# pt100.net
KiCad netlist of a schematic drawn in Altium Designer
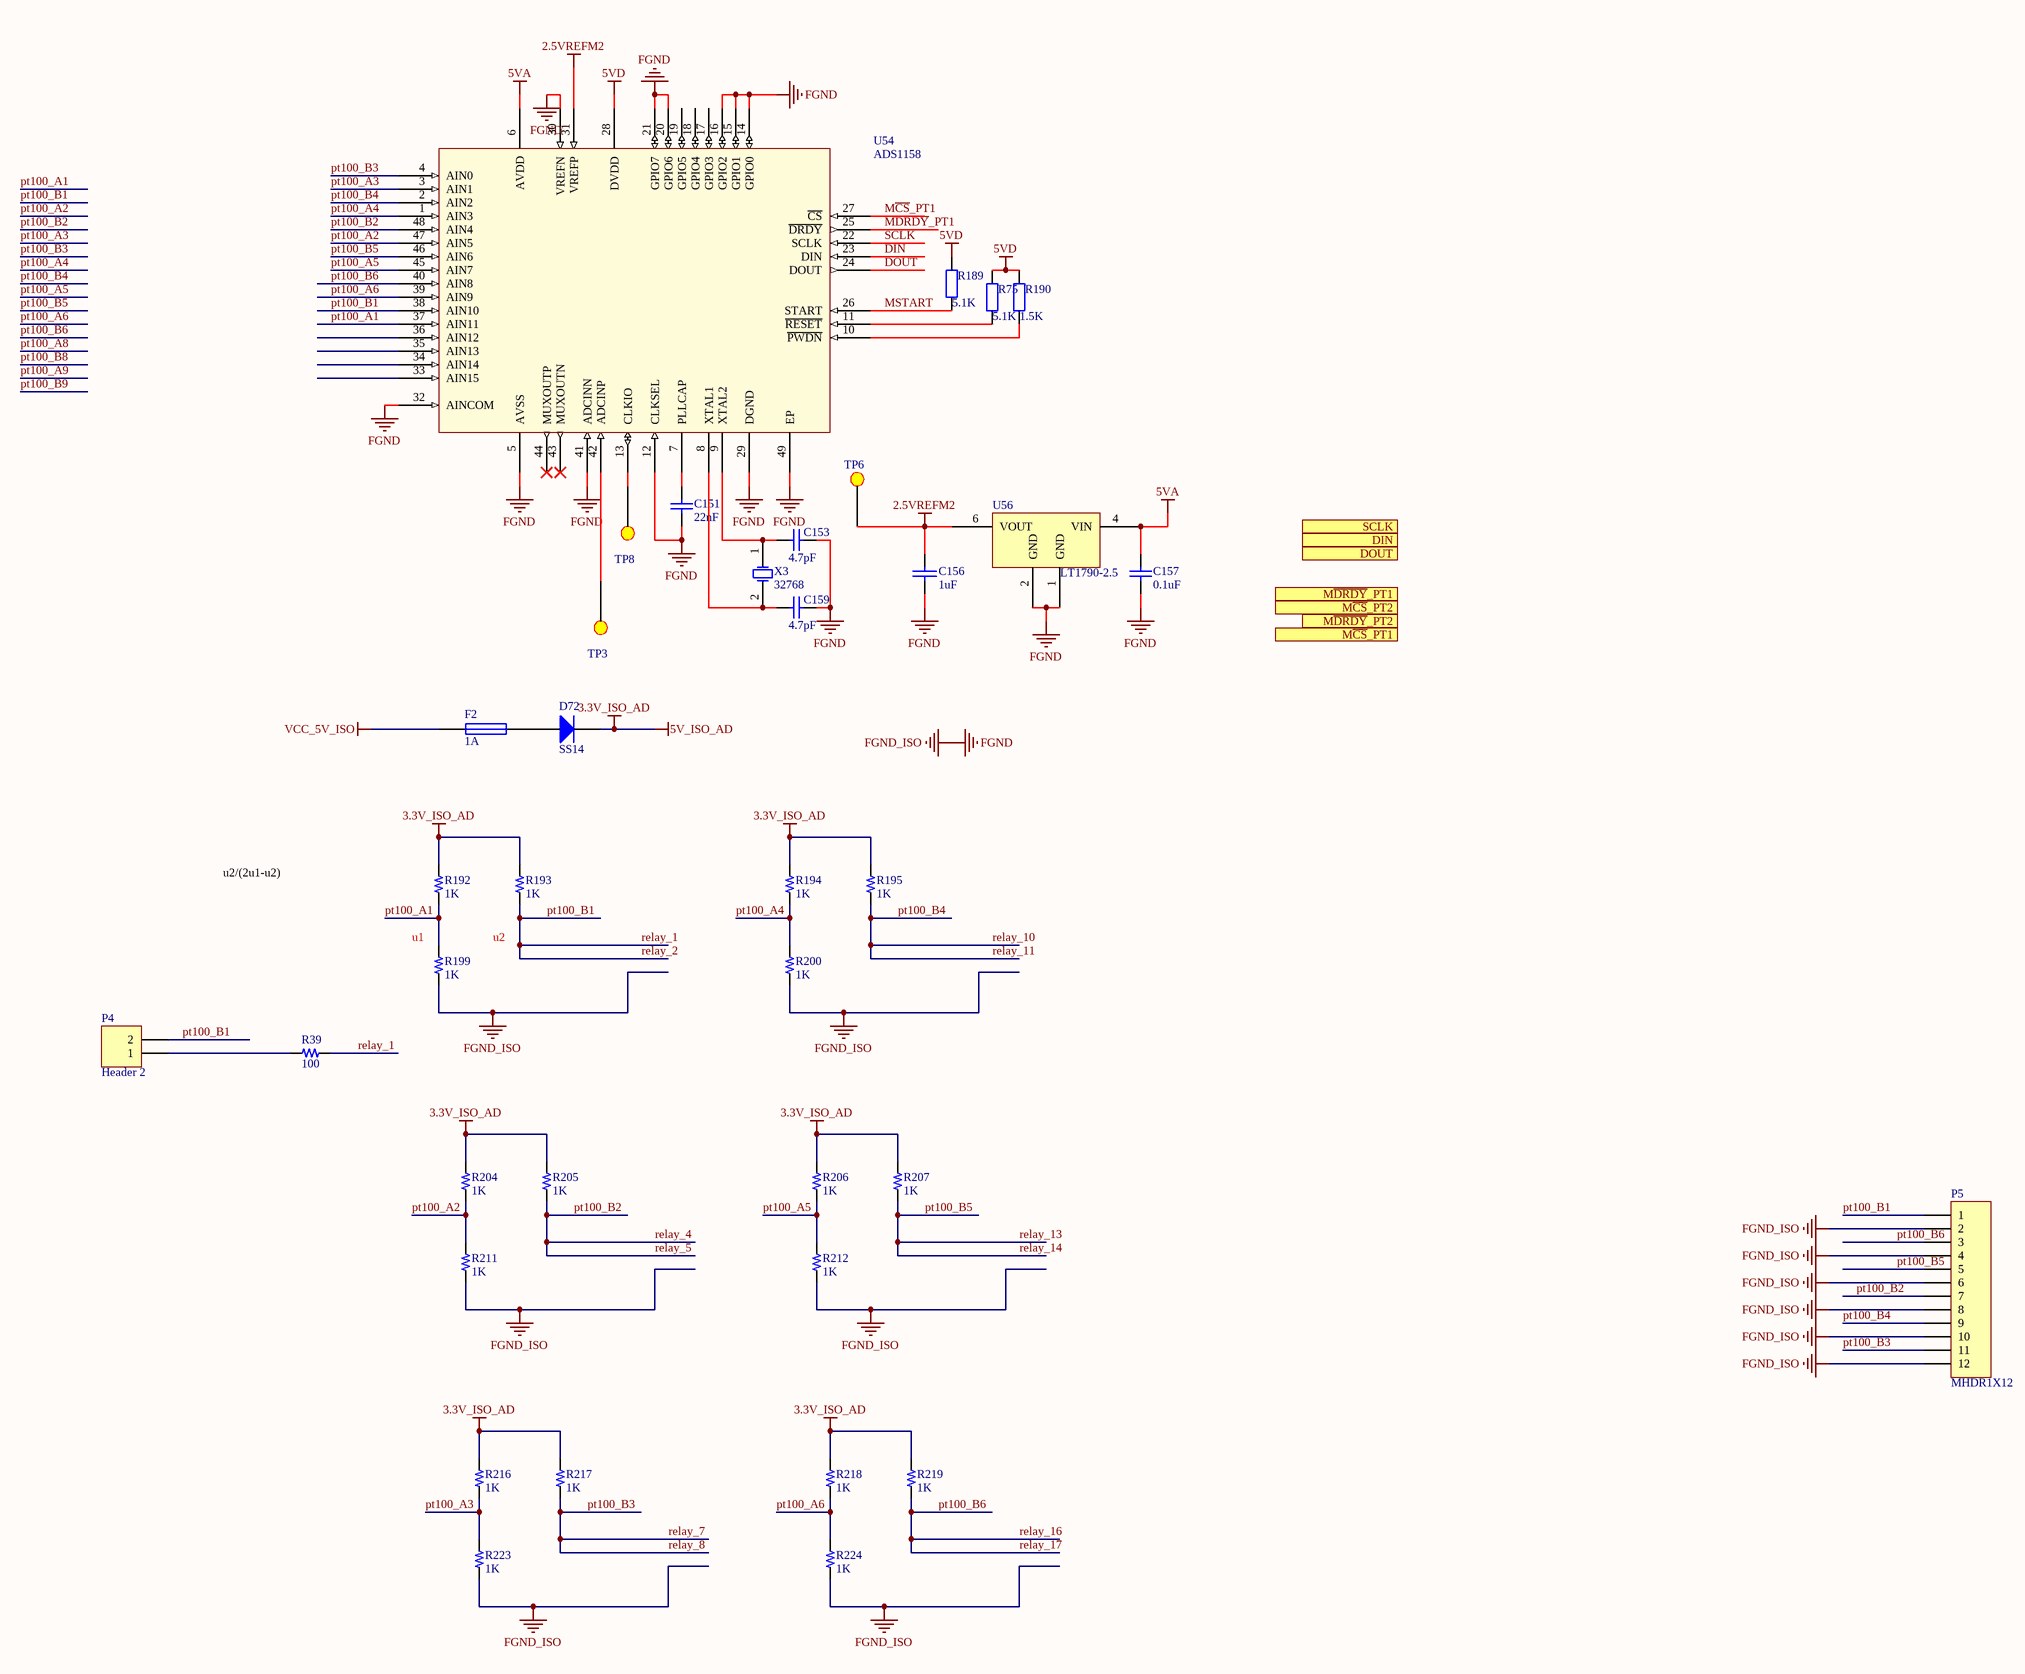
[diagram p0: pt100.SchDoc]

(export (version "E")
  (design (tool "Eeschema 10.0.6"))
  (components
    (comp (ref "C151")
      (value "22nF")
      (footprint "0805C")
      (description "Capacitor")
      (fields (field (name "PUBLISHER") "Altium Limited"))
      (libsource (lib "Miscellaneous Devices") (part "Cap"))
    )
    (comp (ref "C153")
      (value "4.7pF")
      (footprint "0603C")
      (description "Capacitor")
      (fields (field (name "PUBLISHER") "Altium Limited"))
      (libsource (lib "Miscellaneous Devices") (part "Cap"))
    )
    (comp (ref "C156")
      (value "1uF")
      (footprint "0603C")
      (description "Capacitor")
      (libsource (lib "*") (part "CAP"))
    )
    (comp (ref "C157")
      (value "0.1uF")
      (footprint "0603C")
      (description "Capacitor")
      (fields (field (name "PUBLISHER") "Altium Limited"))
      (libsource (lib "Miscellaneous Devices") (part "Cap"))
    )
    (comp (ref "C159")
      (value "4.7pF")
      (footprint "0603C")
      (description "Capacitor")
      (fields (field (name "PUBLISHER") "Altium Limited"))
      (libsource (lib "Miscellaneous Devices") (part "Cap"))
    )
    (comp (ref "D72")
      (value "SS14")
      (footprint "DO-214AC")
      (description "Default Diode")
      (fields (field (name "PUBLISHER") "Altium Limited"))
      (libsource (lib "Miscellaneous Devices") (part "Diode"))
    )
    (comp (ref "F2")
      (value "1A")
      (footprint "0805r")
      (description "Fuse")
      (fields (field (name "PUBLISHER") "Altium Limited"))
      (libsource (lib "Miscellaneous Devices") (part "Fuse 1"))
    )
    (comp (ref "P4")
      (value "Header 2")
      (footprint "HDR1X2")
      (description "Header, 2-Pin")
      (fields (field (name "PUBLISHER") "Altium Limited"))
      (libsource (lib "Miscellaneous Connectors") (part "Header 2"))
    )
    (comp (ref "P5")
      (value "MHDR1X12")
      (footprint "2ETYR-5.08-12P-14-100")
      (description "Header, 12-Pin")
      (fields (field (name "PUBLISHER") "Altium Limited"))
      (libsource (lib "Miscellaneous Connectors") (part "MHDR1X12"))
    )
    (comp (ref "R39")
      (value "100")
      (footprint "0603R")
      (description "R")
      (libsource (lib "JRJ_1") (part "R"))
    )
    (comp (ref "R75") (value "5.1K") (footprint "0603R") (libsource (lib "MQlibrary") (part "Res0805M")))
    (comp (ref "R189") (value "5.1K") (footprint "0603R") (libsource (lib "MQlibrary") (part "Res0805M")))
    (comp (ref "R190") (value "1.5K") (footprint "0603R") (libsource (lib "MQlibrary") (part "Res0805M")))
    (comp (ref "R192")
      (value "1K")
      (footprint "0603R")
      (description "R")
      (libsource (lib "JRJ_1") (part "R"))
    )
    (comp (ref "R193")
      (value "1K")
      (footprint "0603R")
      (description "R")
      (libsource (lib "JRJ_1") (part "R"))
    )
    (comp (ref "R194")
      (value "1K")
      (footprint "0603R")
      (description "R")
      (libsource (lib "JRJ_1") (part "R"))
    )
    (comp (ref "R195")
      (value "1K")
      (footprint "0603R")
      (description "R")
      (libsource (lib "JRJ_1") (part "R"))
    )
    (comp (ref "R199")
      (value "1K")
      (footprint "0603R")
      (description "R")
      (libsource (lib "JRJ_1") (part "R"))
    )
    (comp (ref "R200")
      (value "1K")
      (footprint "0603R")
      (description "R")
      (libsource (lib "JRJ_1") (part "R"))
    )
    (comp (ref "R204")
      (value "1K")
      (footprint "0603R")
      (description "R")
      (libsource (lib "JRJ_1") (part "R"))
    )
    (comp (ref "R205")
      (value "1K")
      (footprint "0603R")
      (description "R")
      (libsource (lib "JRJ_1") (part "R"))
    )
    (comp (ref "R206")
      (value "1K")
      (footprint "0603R")
      (description "R")
      (libsource (lib "JRJ_1") (part "R"))
    )
    (comp (ref "R207")
      (value "1K")
      (footprint "0603R")
      (description "R")
      (libsource (lib "JRJ_1") (part "R"))
    )
    (comp (ref "R211")
      (value "1K")
      (footprint "0603R")
      (description "R")
      (libsource (lib "JRJ_1") (part "R"))
    )
    (comp (ref "R212")
      (value "1K")
      (footprint "0603R")
      (description "R")
      (libsource (lib "JRJ_1") (part "R"))
    )
    (comp (ref "R216")
      (value "1K")
      (footprint "0603R")
      (description "R")
      (libsource (lib "JRJ_1") (part "R"))
    )
    (comp (ref "R217")
      (value "1K")
      (footprint "0603R")
      (description "R")
      (libsource (lib "JRJ_1") (part "R"))
    )
    (comp (ref "R218")
      (value "1K")
      (footprint "0603R")
      (description "R")
      (libsource (lib "JRJ_1") (part "R"))
    )
    (comp (ref "R219")
      (value "1K")
      (footprint "0603R")
      (description "R")
      (libsource (lib "JRJ_1") (part "R"))
    )
    (comp (ref "R223")
      (value "1K")
      (footprint "0603R")
      (description "R")
      (libsource (lib "JRJ_1") (part "R"))
    )
    (comp (ref "R224")
      (value "1K")
      (footprint "0603R")
      (description "R")
      (libsource (lib "JRJ_1") (part "R"))
    )
    (comp (ref "TP3")
      (value "TEST_POINT")
      (footprint "TPD")
      (libsource (lib "基带芯片OEM板_V1P0_张猛_20120921") (part "TEST_POINT"))
    )
    (comp (ref "TP6")
      (value "TEST_POINT")
      (footprint "TPD")
      (libsource (lib "基带芯片OEM板_V1P0_张猛_20120921") (part "TEST_POINT"))
    )
    (comp (ref "TP8")
      (value "TEST_POINT")
      (footprint "TPD")
      (libsource (lib "基带芯片OEM板_V1P0_张猛_20120921") (part "TEST_POINT"))
    )
    (comp (ref "U54")
      (value "ADS1158")
      (footprint "S-PVFQN-N48")
      (description "16-Channel, 16-Bit Analog-to-Digital Converter")
      (libsource (lib "Schlib") (part "ADS1158"))
    )
    (comp (ref "U56")
      (value "LT1790-2.5")
      (footprint "SOT23-6")
      (description "2.5V Micropower SOT-23  Low Dropout Reference")
      (libsource (lib "Schlib") (part "LT1790-2.5"))
    )
    (comp (ref "X3")
      (value "32768")
      (footprint "A")
      (description "Crystal Oscillator")
      (fields (field (name "PUBLISHER") "Altium Limited"))
      (libsource (lib "Miscellaneous Devices") (part "XTAL"))
    )
  )
  (nets
    (net (code "1") (name "/DIN") (class "Default")
      (node (ref "U54") (pin "23") (pinfunction "DIN_23") (pintype "input"))
    )
    (net (code "2") (name "/DOUT") (class "Default")
      (node (ref "U54") (pin "24") (pinfunction "DOUT_24") (pintype "output"))
    )
    (net (code "3") (name "/MSTART") (class "Default")
      (node (ref "R189") (pin "2") (pinfunction "2_2") (pintype "passive"))
      (node (ref "U54") (pin "26") (pinfunction "START_26") (pintype "input"))
    )
    (net (code "4") (name "/M~{CS}_PT1") (class "Default")
      (node (ref "U54") (pin "27") (pinfunction "~{CS}_27") (pintype "input"))
    )
    (net (code "6") (name "/M~{DRDY}_PT1") (class "Default")
      (node (ref "U54") (pin "25") (pinfunction "~{DRDY}_25") (pintype "output"))
    )
    (net (code "8") (name "/SCLK") (class "Default")
      (node (ref "U54") (pin "22") (pinfunction "SCLK_22") (pintype "input"))
    )
    (net (code "9") (name "/pt100_A1") (class "Default")
      (node (ref "R192") (pin "1") (pintype "passive"))
      (node (ref "R199") (pin "2") (pintype "passive"))
      (node (ref "U54") (pin "37") (pinfunction "AIN11_37") (pintype "input"))
    )
    (net (code "10") (name "/pt100_A2") (class "Default")
      (node (ref "R204") (pin "1") (pintype "passive"))
      (node (ref "R211") (pin "2") (pintype "passive"))
      (node (ref "U54") (pin "47") (pinfunction "AIN5_47") (pintype "input"))
    )
    (net (code "11") (name "/pt100_A3") (class "Default")
      (node (ref "R216") (pin "1") (pintype "passive"))
      (node (ref "R223") (pin "2") (pintype "passive"))
      (node (ref "U54") (pin "3") (pinfunction "AIN1_3") (pintype "input"))
    )
    (net (code "12") (name "/pt100_A4") (class "Default")
      (node (ref "R194") (pin "1") (pintype "passive"))
      (node (ref "R200") (pin "2") (pintype "passive"))
      (node (ref "U54") (pin "1") (pinfunction "AIN3_1") (pintype "input"))
    )
    (net (code "13") (name "/pt100_A5") (class "Default")
      (node (ref "R206") (pin "1") (pintype "passive"))
      (node (ref "R212") (pin "2") (pintype "passive"))
      (node (ref "U54") (pin "45") (pinfunction "AIN7_45") (pintype "input"))
    )
    (net (code "14") (name "/pt100_A6") (class "Default")
      (node (ref "R218") (pin "1") (pintype "passive"))
      (node (ref "R224") (pin "2") (pintype "passive"))
      (node (ref "U54") (pin "39") (pinfunction "AIN9_39") (pintype "input"))
    )
    (net (code "17") (name "/pt100_B1") (class "Default")
      (node (ref "P4") (pin "2") (pinfunction "2_2") (pintype "passive"))
      (node (ref "P5") (pin "1") (pinfunction "1_1") (pintype "passive"))
      (node (ref "R193") (pin "1") (pintype "passive"))
      (node (ref "R39") (pin "1") (pintype "passive"))
      (node (ref "U54") (pin "38") (pinfunction "AIN10_38") (pintype "input"))
    )
    (net (code "18") (name "/pt100_B2") (class "Default")
      (node (ref "P5") (pin "7") (pinfunction "7_7") (pintype "passive"))
      (node (ref "R205") (pin "1") (pintype "passive"))
      (node (ref "U54") (pin "48") (pinfunction "AIN4_48") (pintype "input"))
    )
    (net (code "19") (name "/pt100_B3") (class "Default")
      (node (ref "P5") (pin "11") (pinfunction "11_11") (pintype "passive"))
      (node (ref "R217") (pin "1") (pintype "passive"))
      (node (ref "U54") (pin "4") (pinfunction "AIN0_4") (pintype "input"))
    )
    (net (code "20") (name "/pt100_B4") (class "Default")
      (node (ref "P5") (pin "9") (pinfunction "9_9") (pintype "passive"))
      (node (ref "R195") (pin "1") (pintype "passive"))
      (node (ref "U54") (pin "2") (pinfunction "AIN2_2") (pintype "input"))
    )
    (net (code "21") (name "/pt100_B5") (class "Default")
      (node (ref "P5") (pin "5") (pinfunction "5_5") (pintype "passive"))
      (node (ref "R207") (pin "1") (pintype "passive"))
      (node (ref "U54") (pin "46") (pinfunction "AIN6_46") (pintype "input"))
    )
    (net (code "22") (name "/pt100_B6") (class "Default")
      (node (ref "P5") (pin "3") (pinfunction "3_3") (pintype "passive"))
      (node (ref "R219") (pin "1") (pintype "passive"))
      (node (ref "U54") (pin "40") (pinfunction "AIN8_40") (pintype "input"))
    )
    (net (code "25") (name "2.5VREFM2") (class "Default")
      (node (ref "C156") (pin "1") (pinfunction "1_1") (pintype "passive"))
      (node (ref "TP6") (pin "1") (pinfunction "1_1") (pintype "passive"))
      (node (ref "U54") (pin "31") (pinfunction "VREFP_31") (pintype "input"))
      (node (ref "U56") (pin "6") (pinfunction "VOUT_6") (pintype "power_in"))
    )
    (net (code "26") (name "3.3V_ISO_AD") (class "Default")
      (node (ref "D72") (pin "2") (pinfunction "K_2") (pintype "passive"))
      (node (ref "R192") (pin "2") (pintype "passive"))
      (node (ref "R193") (pin "2") (pintype "passive"))
      (node (ref "R194") (pin "2") (pintype "passive"))
      (node (ref "R195") (pin "2") (pintype "passive"))
      (node (ref "R204") (pin "2") (pintype "passive"))
      (node (ref "R205") (pin "2") (pintype "passive"))
      (node (ref "R206") (pin "2") (pintype "passive"))
      (node (ref "R207") (pin "2") (pintype "passive"))
      (node (ref "R216") (pin "2") (pintype "passive"))
      (node (ref "R217") (pin "2") (pintype "passive"))
      (node (ref "R218") (pin "2") (pintype "passive"))
      (node (ref "R219") (pin "2") (pintype "passive"))
    )
    (net (code "27") (name "5VA") (class "Default")
      (node (ref "C157") (pin "2") (pinfunction "2_2") (pintype "passive"))
      (node (ref "U54") (pin "6") (pinfunction "AVDD_6") (pintype "passive"))
      (node (ref "U56") (pin "4") (pinfunction "VIN_4") (pintype "power_in"))
    )
    (net (code "28") (name "5VD") (class "Default")
      (node (ref "R189") (pin "1") (pinfunction "1_1") (pintype "passive"))
      (node (ref "R190") (pin "1") (pinfunction "1_1") (pintype "passive"))
      (node (ref "R75") (pin "1") (pinfunction "1_1") (pintype "passive"))
      (node (ref "U54") (pin "28") (pinfunction "DVDD_28") (pintype "power_in"))
    )
    (net (code "29") (name "FGND") (class "Default")
      (node (ref "C151") (pin "2") (pinfunction "2_2") (pintype "passive"))
      (node (ref "C153") (pin "2") (pinfunction "2_2") (pintype "passive"))
      (node (ref "C156") (pin "2") (pinfunction "2_2") (pintype "passive"))
      (node (ref "C157") (pin "1") (pinfunction "1_1") (pintype "passive"))
      (node (ref "C159") (pin "2") (pinfunction "2_2") (pintype "passive"))
      (node (ref "P5") (pin "10") (pinfunction "10_10") (pintype "passive"))
      (node (ref "P5") (pin "12") (pinfunction "12_12") (pintype "passive"))
      (node (ref "P5") (pin "2") (pinfunction "2_2") (pintype "passive"))
      (node (ref "P5") (pin "4") (pinfunction "4_4") (pintype "passive"))
      (node (ref "P5") (pin "6") (pinfunction "6_6") (pintype "passive"))
      (node (ref "P5") (pin "8") (pinfunction "8_8") (pintype "passive"))
      (node (ref "R199") (pin "1") (pintype "passive"))
      (node (ref "R200") (pin "1") (pintype "passive"))
      (node (ref "R211") (pin "1") (pintype "passive"))
      (node (ref "R212") (pin "1") (pintype "passive"))
      (node (ref "R223") (pin "1") (pintype "passive"))
      (node (ref "R224") (pin "1") (pintype "passive"))
      (node (ref "U54") (pin "12") (pinfunction "CLKSEL_12") (pintype "input"))
      (node (ref "U54") (pin "14") (pinfunction "GPIO0_14") (pintype "bidirectional"))
      (node (ref "U54") (pin "15") (pinfunction "GPIO1_15") (pintype "bidirectional"))
      (node (ref "U54") (pin "16") (pinfunction "GPIO2_16") (pintype "bidirectional"))
      (node (ref "U54") (pin "20") (pinfunction "GPIO6_20") (pintype "bidirectional"))
      (node (ref "U54") (pin "21") (pinfunction "GPIO7_21") (pintype "bidirectional"))
      (node (ref "U54") (pin "29") (pinfunction "DGND_29") (pintype "power_in"))
      (node (ref "U54") (pin "30") (pinfunction "VREFN_30") (pintype "input"))
      (node (ref "U54") (pin "32") (pinfunction "AINCOM_32") (pintype "input"))
      (node (ref "U54") (pin "41") (pinfunction "ADCINN_41") (pintype "input"))
      (node (ref "U54") (pin "49") (pinfunction "EP_49") (pintype "passive"))
      (node (ref "U54") (pin "5") (pinfunction "AVSS_5") (pintype "power_in"))
      (node (ref "U56") (pin "1") (pinfunction "GND_1") (pintype "power_in"))
      (node (ref "U56") (pin "2") (pinfunction "GND_2") (pintype "power_in"))
    )
    (net (code "30") (name "Net-(D72-A)") (class "Default")
      (node (ref "D72") (pin "1") (pinfunction "A_1") (pintype "passive"))
      (node (ref "F2") (pin "2") (pinfunction "2_2") (pintype "passive"))
    )
    (net (code "31") (name "Net-(P4-Pad1)") (class "Default")
      (node (ref "P4") (pin "1") (pinfunction "1_1") (pintype "passive"))
      (node (ref "R39") (pin "2") (pintype "passive"))
    )
    (net (code "32") (name "Net-(U54-ADCINP)") (class "Default")
      (node (ref "TP3") (pin "1") (pinfunction "1_1") (pintype "passive"))
      (node (ref "U54") (pin "42") (pinfunction "ADCINP_42") (pintype "input"))
    )
    (net (code "33") (name "Net-(U54-CLKIO)") (class "Default")
      (node (ref "TP8") (pin "1") (pinfunction "1_1") (pintype "passive"))
      (node (ref "U54") (pin "13") (pinfunction "CLKIO_13") (pintype "bidirectional"))
    )
    (net (code "34") (name "Net-(U54-PLLCAP)") (class "Default")
      (node (ref "C151") (pin "1") (pinfunction "1_1") (pintype "passive"))
      (node (ref "U54") (pin "7") (pinfunction "PLLCAP_7") (pintype "power_in"))
    )
    (net (code "35") (name "Net-(U54-XTAL1)") (class "Default")
      (node (ref "C159") (pin "1") (pinfunction "1_1") (pintype "passive"))
      (node (ref "U54") (pin "8") (pinfunction "XTAL1_8") (pintype "passive"))
      (node (ref "X3") (pin "2") (pinfunction "OSC2_2") (pintype "passive"))
    )
    (net (code "36") (name "Net-(U54-XTAL2)") (class "Default")
      (node (ref "C153") (pin "1") (pinfunction "1_1") (pintype "passive"))
      (node (ref "U54") (pin "9") (pinfunction "XTAL2_9") (pintype "passive"))
      (node (ref "X3") (pin "1") (pinfunction "OSC1_1") (pintype "passive"))
    )
    (net (code "37") (name "Net-(U54-~{PWDN})") (class "Default")
      (node (ref "R190") (pin "2") (pinfunction "2_2") (pintype "passive"))
      (node (ref "U54") (pin "10") (pinfunction "~{PWDN}_10") (pintype "input"))
    )
    (net (code "38") (name "Net-(U54-~{RESET})") (class "Default")
      (node (ref "R75") (pin "2") (pinfunction "2_2") (pintype "passive"))
      (node (ref "U54") (pin "11") (pinfunction "~{RESET}_11") (pintype "input"))
    )
    (net (code "39") (name "VCC_5V_ISO") (class "Default")
      (node (ref "F2") (pin "1") (pinfunction "1_1") (pintype "passive"))
    )
    (net (code "40") (name "unconnected-(U54-AIN12-Pad36)") (class "Default")
      (node (ref "U54") (pin "36") (pinfunction "AIN12_36") (pintype "input"))
    )
    (net (code "41") (name "unconnected-(U54-AIN13-Pad35)") (class "Default")
      (node (ref "U54") (pin "35") (pinfunction "AIN13_35") (pintype "input"))
    )
    (net (code "42") (name "unconnected-(U54-AIN14-Pad34)") (class "Default")
      (node (ref "U54") (pin "34") (pinfunction "AIN14_34") (pintype "input"))
    )
    (net (code "43") (name "unconnected-(U54-AIN15-Pad33)") (class "Default")
      (node (ref "U54") (pin "33") (pinfunction "AIN15_33") (pintype "input"))
    )
    (net (code "44") (name "unconnected-(U54-GPIO3-Pad17)") (class "Default")
      (node (ref "U54") (pin "17") (pinfunction "GPIO3_17") (pintype "bidirectional"))
    )
    (net (code "45") (name "unconnected-(U54-GPIO4-Pad18)") (class "Default")
      (node (ref "U54") (pin "18") (pinfunction "GPIO4_18") (pintype "bidirectional"))
    )
    (net (code "46") (name "unconnected-(U54-GPIO5-Pad19)") (class "Default")
      (node (ref "U54") (pin "19") (pinfunction "GPIO5_19") (pintype "bidirectional"))
    )
    (net (code "47") (name "unconnected-(U54-MUXOUTN-Pad43)") (class "Default")
      (node (ref "U54") (pin "43") (pinfunction "MUXOUTN_43") (pintype "output+no_connect"))
    )
    (net (code "48") (name "unconnected-(U54-MUXOUTP-Pad44)") (class "Default")
      (node (ref "U54") (pin "44") (pinfunction "MUXOUTP_44") (pintype "output+no_connect"))
    )
    (net (code "49") (name "unconnected-(U56-DNC-Pad3)") (class "Default")
      (node (ref "U56") (pin "3") (pinfunction "DNC_3") (pintype "passive"))
    )
    (net (code "50") (name "unconnected-(U56-DNC-Pad5)") (class "Default")
      (node (ref "U56") (pin "5") (pinfunction "DNC_5") (pintype "passive"))
    )
  )
)
